# kelvin_1wire_B.net
KiCad netlist of a schematic drawn in EAGLE
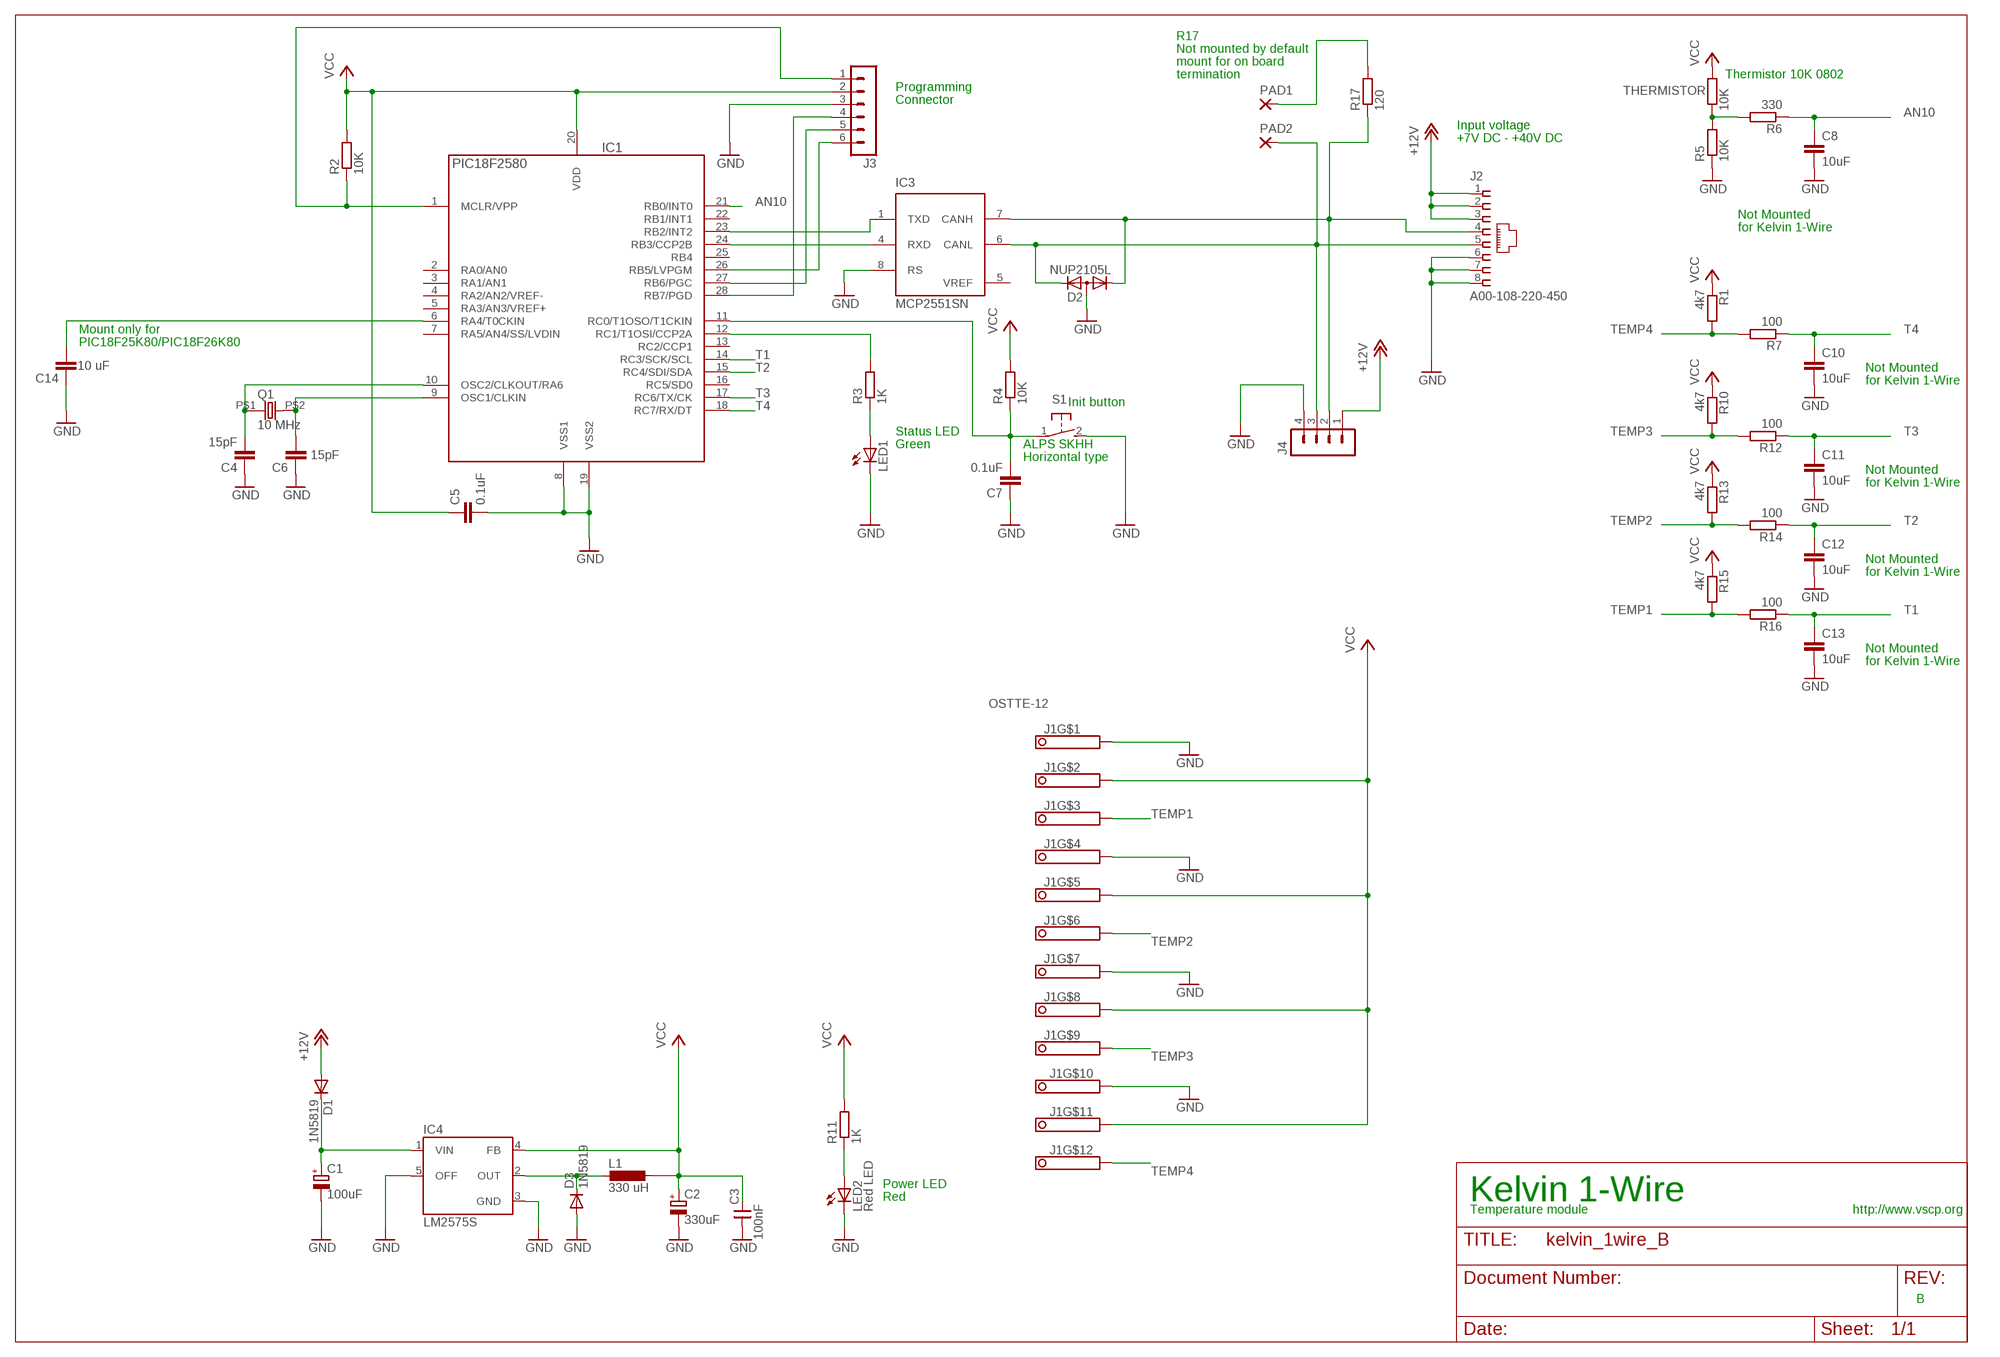
[diagram p0: schematic, sheet 1]

(export (version "E")
  (design (tool "Eeschema 10.0.6"))
  (components
    (comp (ref "C1")
      (value "100uF")
      (footprint "eagle-import:PANASONIC_D")
      (libsource (lib "eagle-import") (part "CPOL-EUD"))
    )
    (comp (ref "C2")
      (value "330uF")
      (footprint "eagle-import:PANASONIC_D")
      (libsource (lib "eagle-import") (part "CPOL-EUD"))
    )
    (comp (ref "C3")
      (value "100nF")
      (footprint "eagle-import:0805")
      (libsource (lib "eagle-import") (part "CNP-0805"))
    )
    (comp (ref "C4")
      (value "15pF")
      (footprint "eagle-import:C0805")
      (libsource (lib "eagle-import") (part "C-EUC0805"))
    )
    (comp (ref "C5")
      (value "0.1uF")
      (footprint "eagle-import:C0805")
      (libsource (lib "eagle-import") (part "C-EUC0805"))
    )
    (comp (ref "C6")
      (value "15pF")
      (footprint "eagle-import:C0805")
      (libsource (lib "eagle-import") (part "C-EUC0805"))
    )
    (comp (ref "C7")
      (value "0.1uF")
      (footprint "eagle-import:C0805")
      (libsource (lib "eagle-import") (part "C-EUC0805"))
    )
    (comp (ref "C8")
      (value "10uF")
      (footprint "eagle-import:C0805")
      (libsource (lib "eagle-import") (part "C-EUC0805"))
    )
    (comp (ref "C10")
      (value "10uF")
      (footprint "eagle-import:C0805")
      (libsource (lib "eagle-import") (part "C-EUC0805"))
    )
    (comp (ref "C11")
      (value "10uF")
      (footprint "eagle-import:C0805")
      (libsource (lib "eagle-import") (part "C-EUC0805"))
    )
    (comp (ref "C12")
      (value "10uF")
      (footprint "eagle-import:C0805")
      (libsource (lib "eagle-import") (part "C-EUC0805"))
    )
    (comp (ref "C13")
      (value "10uF")
      (footprint "eagle-import:C0805")
      (libsource (lib "eagle-import") (part "C-EUC0805"))
    )
    (comp (ref "C14")
      (value "10 uF")
      (footprint "eagle-import:C0805")
      (libsource (lib "eagle-import") (part "C-EUC0805"))
    )
    (comp (ref "D1")
      (value "1N5819")
      (footprint "eagle-import:SOD123")
      (libsource (lib "eagle-import") (part "DIODE-SOD123"))
    )
    (comp (ref "D2")
      (value "NUP2105L")
      (footprint "eagle-import:SOT23")
      (libsource (lib "eagle-import") (part "DIODE-2CA|ACSOT23"))
    )
    (comp (ref "D3")
      (value "1N5819")
      (footprint "eagle-import:SOD123")
      (libsource (lib "eagle-import") (part "DIODE-SOD123"))
    )
    (comp (ref "IC1")
      (value "PIC18F2580")
      (footprint "eagle-import:SO28")
      (libsource (lib "eagle-import") (part "PIC18F252-?I/SOL"))
    )
    (comp (ref "IC3")
      (value "MCP2551SN")
      (footprint "eagle-import:SO-08")
      (libsource (lib "eagle-import") (part "MCP2551SN"))
    )
    (comp (ref "IC4")
      (value "LM2575S")
      (footprint "eagle-import:TO263-5")
      (libsource (lib "eagle-import") (part "LM2575S"))
    )
    (comp (ref "J1")
      (value "OSTTE-12")
      (footprint "eagle-import:PINHEAD-12")
      (libsource (lib "eagle-import") (part "OSTTE-12"))
    )
    (comp (ref "J2")
      (value "A00-108-220-450")
      (footprint "eagle-import:RJ-45")
      (libsource (lib "eagle-import") (part "A00-108-220-450"))
    )
    (comp (ref "J3")
      (value "MA06-1")
      (footprint "eagle-import:MA06-1")
      (libsource (lib "eagle-import") (part "MA06-1"))
    )
    (comp (ref "J4")
      (value "MA04-1")
      (footprint "eagle-import:MA04-1")
      (libsource (lib "eagle-import") (part "MA04-1"))
    )
    (comp (ref "L1")
      (value "330 uH")
      (footprint "eagle-import:DO3316P")
      (libsource (lib "eagle-import") (part "DO3316P"))
    )
    (comp (ref "LED1")
      (value "LEDCHIP-LED0805")
      (footprint "eagle-import:CHIP-LED0805")
      (libsource (lib "eagle-import") (part "LEDCHIP-LED0805"))
    )
    (comp (ref "LED2")
      (value "Red LED")
      (footprint "eagle-import:CHIP-LED0805")
      (libsource (lib "eagle-import") (part "LEDCHIP-LED0805"))
    )
    (comp (ref "PAD1")
      (value "1,6/0,8")
      (footprint "eagle-import:1,6_0,8")
      (libsource (lib "eagle-import") (part "1,6/0,8"))
    )
    (comp (ref "PAD2")
      (value "1,6/0,8")
      (footprint "eagle-import:1,6_0,8")
      (libsource (lib "eagle-import") (part "1,6/0,8"))
    )
    (comp (ref "Q1")
      (value "10 MHz")
      (footprint "eagle-import:9C")
      (libsource (lib "eagle-import") (part "HC-49S"))
    )
    (comp (ref "R1")
      (value "4k7")
      (footprint "eagle-import:R0805")
      (libsource (lib "eagle-import") (part "R-EU_R0805"))
    )
    (comp (ref "R2")
      (value "10K")
      (footprint "eagle-import:R0805")
      (libsource (lib "eagle-import") (part "R-EU_R0805"))
    )
    (comp (ref "R3")
      (value "1K")
      (footprint "eagle-import:R0805")
      (libsource (lib "eagle-import") (part "R-EU_R0805"))
    )
    (comp (ref "R4")
      (value "10K")
      (footprint "eagle-import:R0805")
      (libsource (lib "eagle-import") (part "R-EU_R0805"))
    )
    (comp (ref "R5")
      (value "10K")
      (footprint "eagle-import:R0805")
      (libsource (lib "eagle-import") (part "R-EU_R0805"))
    )
    (comp (ref "R6")
      (value "330")
      (footprint "eagle-import:R0805")
      (libsource (lib "eagle-import") (part "R-EU_R0805"))
    )
    (comp (ref "R7")
      (value "100")
      (footprint "eagle-import:R0805")
      (libsource (lib "eagle-import") (part "R-EU_R0805"))
    )
    (comp (ref "R10")
      (value "4k7")
      (footprint "eagle-import:R0805")
      (libsource (lib "eagle-import") (part "R-EU_R0805"))
    )
    (comp (ref "R11")
      (value "1K")
      (footprint "eagle-import:R0805")
      (libsource (lib "eagle-import") (part "R-EU_R0805"))
    )
    (comp (ref "R12")
      (value "100")
      (footprint "eagle-import:R0805")
      (libsource (lib "eagle-import") (part "R-EU_R0805"))
    )
    (comp (ref "R13")
      (value "4k7")
      (footprint "eagle-import:R0805")
      (libsource (lib "eagle-import") (part "R-EU_R0805"))
    )
    (comp (ref "R14")
      (value "100")
      (footprint "eagle-import:R0805")
      (libsource (lib "eagle-import") (part "R-EU_R0805"))
    )
    (comp (ref "R15")
      (value "4k7")
      (footprint "eagle-import:R0805")
      (libsource (lib "eagle-import") (part "R-EU_R0805"))
    )
    (comp (ref "R16")
      (value "100")
      (footprint "eagle-import:R0805")
      (libsource (lib "eagle-import") (part "R-EU_R0805"))
    )
    (comp (ref "R17")
      (value "120")
      (footprint "eagle-import:R0805")
      (libsource (lib "eagle-import") (part "R-EU_R0805"))
    )
    (comp (ref "S1")
      (value "31-XX")
      (footprint "eagle-import:B3F-31XX")
      (fields (field (name "MPN") "B3F-3100"))
      (libsource (lib "eagle-import") (part "31-XX"))
    )
    (comp (ref "THERMISTOR")
      (value "10K")
      (footprint "eagle-import:R0805")
      (libsource (lib "eagle-import") (part "R-EU_R0805"))
    )
  )
  (nets
    (net (code "1") (name "+12V") (class "Default")
      (node (ref "D1") (pin "A") (pinfunction "A_A") (pintype "passive"))
      (node (ref "J2") (pin "1") (pinfunction "1_1") (pintype "passive"))
      (node (ref "J2") (pin "2") (pinfunction "2_2") (pintype "passive"))
      (node (ref "J2") (pin "3") (pinfunction "3_3") (pintype "passive"))
      (node (ref "J4") (pin "1") (pinfunction "1_1") (pintype "passive"))
    )
    (net (code "2") (name "/AN10") (class "Default")
      (node (ref "C8") (pin "1") (pinfunction "1_1") (pintype "passive"))
      (node (ref "IC1") (pin "21") (pinfunction "RB0/INT0_21") (pintype "bidirectional"))
      (node (ref "R6") (pin "1") (pinfunction "1_1") (pintype "passive"))
    )
    (net (code "3") (name "/T1") (class "Default")
      (node (ref "C13") (pin "1") (pinfunction "1_1") (pintype "passive"))
      (node (ref "IC1") (pin "14") (pinfunction "RC3/SCK/SCL_14") (pintype "bidirectional"))
      (node (ref "R16") (pin "1") (pinfunction "1_1") (pintype "passive"))
    )
    (net (code "4") (name "/T2") (class "Default")
      (node (ref "C12") (pin "1") (pinfunction "1_1") (pintype "passive"))
      (node (ref "IC1") (pin "15") (pinfunction "RC4/SDI/SDA_15") (pintype "bidirectional"))
      (node (ref "R14") (pin "1") (pinfunction "1_1") (pintype "passive"))
    )
    (net (code "5") (name "/T3") (class "Default")
      (node (ref "C11") (pin "1") (pinfunction "1_1") (pintype "passive"))
      (node (ref "IC1") (pin "17") (pinfunction "RC6/TX/CK_17") (pintype "bidirectional"))
      (node (ref "R12") (pin "1") (pinfunction "1_1") (pintype "passive"))
    )
    (net (code "6") (name "/T4") (class "Default")
      (node (ref "C10") (pin "1") (pinfunction "1_1") (pintype "passive"))
      (node (ref "IC1") (pin "18") (pinfunction "RC7/RX/DT_18") (pintype "bidirectional"))
      (node (ref "R7") (pin "1") (pinfunction "1_1") (pintype "passive"))
    )
    (net (code "7") (name "/TEMP1") (class "Default")
      (node (ref "J1") (pin "3") (pinfunction "K_3") (pintype "passive"))
      (node (ref "R15") (pin "2") (pinfunction "2_2") (pintype "passive"))
      (node (ref "R16") (pin "2") (pinfunction "2_2") (pintype "passive"))
    )
    (net (code "8") (name "/TEMP2") (class "Default")
      (node (ref "J1") (pin "6") (pinfunction "K_6") (pintype "passive"))
      (node (ref "R13") (pin "2") (pinfunction "2_2") (pintype "passive"))
      (node (ref "R14") (pin "2") (pinfunction "2_2") (pintype "passive"))
    )
    (net (code "9") (name "/TEMP3") (class "Default")
      (node (ref "J1") (pin "9") (pinfunction "K_9") (pintype "passive"))
      (node (ref "R10") (pin "2") (pinfunction "2_2") (pintype "passive"))
      (node (ref "R12") (pin "2") (pinfunction "2_2") (pintype "passive"))
    )
    (net (code "10") (name "/TEMP4") (class "Default")
      (node (ref "J1") (pin "12") (pinfunction "K_12") (pintype "passive"))
      (node (ref "R1") (pin "2") (pinfunction "2_2") (pintype "passive"))
      (node (ref "R7") (pin "2") (pinfunction "2_2") (pintype "passive"))
    )
    (net (code "11") (name "/VREF") (class "Default")
      (node (ref "IC3") (pin "5") (pinfunction "VREF_5") (pintype "power_in"))
    )
    (net (code "12") (name "GND") (class "Default")
      (node (ref "C1") (pin "-") (pinfunction "-_-") (pintype "passive"))
      (node (ref "C10") (pin "2") (pinfunction "2_2") (pintype "passive"))
      (node (ref "C11") (pin "2") (pinfunction "2_2") (pintype "passive"))
      (node (ref "C12") (pin "2") (pinfunction "2_2") (pintype "passive"))
      (node (ref "C13") (pin "2") (pinfunction "2_2") (pintype "passive"))
      (node (ref "C14") (pin "1") (pinfunction "1_1") (pintype "passive"))
      (node (ref "C2") (pin "-") (pinfunction "-_-") (pintype "passive"))
      (node (ref "C3") (pin "1") (pinfunction "1_1") (pintype "passive"))
      (node (ref "C4") (pin "1") (pinfunction "1_1") (pintype "passive"))
      (node (ref "C5") (pin "2") (pinfunction "2_2") (pintype "passive"))
      (node (ref "C6") (pin "1") (pinfunction "1_1") (pintype "passive"))
      (node (ref "C7") (pin "1") (pinfunction "1_1") (pintype "passive"))
      (node (ref "C8") (pin "2") (pinfunction "2_2") (pintype "passive"))
      (node (ref "D2") (pin "3") (pinfunction "A_3") (pintype "passive"))
      (node (ref "D3") (pin "A") (pinfunction "A_A") (pintype "passive"))
      (node (ref "IC1") (pin "19") (pinfunction "VSS2_19") (pintype "power_in"))
      (node (ref "IC1") (pin "8") (pinfunction "VSS1_8") (pintype "power_in"))
      (node (ref "IC3") (pin "8") (pinfunction "RS_8") (pintype "input"))
      (node (ref "IC4") (pin "3") (pinfunction "GND_3") (pintype "power_in"))
      (node (ref "IC4") (pin "5") (pinfunction "OFF_5") (pintype "input"))
      (node (ref "J1") (pin "1") (pinfunction "K_1") (pintype "passive"))
      (node (ref "J1") (pin "10") (pinfunction "K_10") (pintype "passive"))
      (node (ref "J1") (pin "4") (pinfunction "K_4") (pintype "passive"))
      (node (ref "J1") (pin "7") (pinfunction "K_7") (pintype "passive"))
      (node (ref "J2") (pin "6") (pinfunction "6_6") (pintype "passive"))
      (node (ref "J2") (pin "7") (pinfunction "7_7") (pintype "passive"))
      (node (ref "J2") (pin "8") (pinfunction "8_8") (pintype "passive"))
      (node (ref "J3") (pin "3") (pinfunction "3_3") (pintype "passive"))
      (node (ref "J4") (pin "4") (pinfunction "4_4") (pintype "passive"))
      (node (ref "LED1") (pin "C") (pinfunction "C_C") (pintype "passive"))
      (node (ref "LED2") (pin "C") (pinfunction "C_C") (pintype "passive"))
      (node (ref "R5") (pin "1") (pinfunction "1_1") (pintype "passive"))
      (node (ref "S1") (pin "2") (pinfunction "S_2") (pintype "passive"))
    )
    (net (code "13") (name "Net-(D2-K1)") (class "Default")
      (node (ref "D2") (pin "1") (pinfunction "K1_1") (pintype "passive"))
      (node (ref "IC3") (pin "7") (pinfunction "CANH_7") (pintype "bidirectional"))
      (node (ref "J2") (pin "4") (pinfunction "4_4") (pintype "passive"))
      (node (ref "J4") (pin "2") (pinfunction "2_2") (pintype "passive"))
      (node (ref "R17") (pin "1") (pinfunction "1_1") (pintype "passive"))
    )
    (net (code "14") (name "Net-(D2-K2)") (class "Default")
      (node (ref "D2") (pin "2") (pinfunction "K2_2") (pintype "passive"))
      (node (ref "IC3") (pin "6") (pinfunction "CANL_6") (pintype "bidirectional"))
      (node (ref "J2") (pin "5") (pinfunction "5_5") (pintype "passive"))
      (node (ref "J4") (pin "3") (pinfunction "3_3") (pintype "passive"))
      (node (ref "PAD2") (pin "1") (pinfunction "P_1") (pintype "passive"))
    )
    (net (code "15") (name "Net-(IC1-MCLR{slash}VPP)") (class "Default")
      (node (ref "IC1") (pin "1") (pinfunction "MCLR/VPP_1") (pintype "input"))
      (node (ref "J3") (pin "1") (pinfunction "1_1") (pintype "passive"))
      (node (ref "R2") (pin "1") (pinfunction "1_1") (pintype "passive"))
    )
    (net (code "16") (name "Net-(IC1-OSC1{slash}CLKIN)") (class "Default")
      (node (ref "C6") (pin "2") (pinfunction "2_2") (pintype "passive"))
      (node (ref "IC1") (pin "9") (pinfunction "OSC1/CLKIN_9") (pintype "input"))
      (node (ref "Q1") (pin "P$2") (pinfunction "2_P$2") (pintype "passive"))
    )
    (net (code "17") (name "Net-(IC1-OSC2{slash}CLKOUT{slash}RA6)") (class "Default")
      (node (ref "C4") (pin "2") (pinfunction "2_2") (pintype "passive"))
      (node (ref "IC1") (pin "10") (pinfunction "OSC2/CLKOUT/RA6_10") (pintype "output"))
      (node (ref "Q1") (pin "P$1") (pinfunction "1_P$1") (pintype "passive"))
    )
    (net (code "18") (name "Net-(IC1-RA4{slash}T0CKIN)") (class "Default")
      (node (ref "C14") (pin "2") (pinfunction "2_2") (pintype "passive"))
      (node (ref "IC1") (pin "6") (pinfunction "RA4/T0CKIN_6") (pintype "open_collector"))
    )
    (net (code "19") (name "Net-(IC1-RB2{slash}INT2)") (class "Default")
      (node (ref "IC1") (pin "23") (pinfunction "RB2/INT2_23") (pintype "bidirectional"))
      (node (ref "IC3") (pin "1") (pinfunction "TXD_1") (pintype "input"))
    )
    (net (code "20") (name "Net-(IC1-RB3{slash}CCP2B)") (class "Default")
      (node (ref "IC1") (pin "24") (pinfunction "RB3/CCP2B_24") (pintype "bidirectional"))
      (node (ref "IC3") (pin "4") (pinfunction "RXD_4") (pintype "output"))
    )
    (net (code "21") (name "Net-(IC1-RB5{slash}LVPGM)") (class "Default")
      (node (ref "IC1") (pin "26") (pinfunction "RB5/LVPGM_26") (pintype "bidirectional"))
      (node (ref "J3") (pin "6") (pinfunction "6_6") (pintype "passive"))
    )
    (net (code "22") (name "Net-(IC1-RB6{slash}PGC)") (class "Default")
      (node (ref "IC1") (pin "27") (pinfunction "RB6/PGC_27") (pintype "bidirectional"))
      (node (ref "J3") (pin "5") (pinfunction "5_5") (pintype "passive"))
    )
    (net (code "23") (name "Net-(IC1-RB7{slash}PGD)") (class "Default")
      (node (ref "IC1") (pin "28") (pinfunction "RB7/PGD_28") (pintype "bidirectional"))
      (node (ref "J3") (pin "4") (pinfunction "4_4") (pintype "passive"))
    )
    (net (code "24") (name "Net-(IC1-RC0{slash}T1OSO{slash}T1CKIN)") (class "Default")
      (node (ref "C7") (pin "2") (pinfunction "2_2") (pintype "passive"))
      (node (ref "IC1") (pin "11") (pinfunction "RC0/T1OSO/T1CKIN_11") (pintype "bidirectional"))
      (node (ref "R4") (pin "1") (pinfunction "1_1") (pintype "passive"))
      (node (ref "S1") (pin "1") (pinfunction "P_1") (pintype "passive"))
    )
    (net (code "25") (name "Net-(IC1-RC1{slash}T1OSI{slash}CCP2A)") (class "Default")
      (node (ref "IC1") (pin "12") (pinfunction "RC1/T1OSI/CCP2A_12") (pintype "bidirectional"))
      (node (ref "R3") (pin "2") (pinfunction "2_2") (pintype "passive"))
    )
    (net (code "26") (name "Net-(IC4-OUT)") (class "Default")
      (node (ref "D3") (pin "C") (pinfunction "C_C") (pintype "passive"))
      (node (ref "IC4") (pin "2") (pinfunction "OUT_2") (pintype "output"))
      (node (ref "L1") (pin "1") (pinfunction "1_1") (pintype "passive"))
    )
    (net (code "27") (name "Net-(IC4-VIN)") (class "Default")
      (node (ref "C1") (pin "+") (pinfunction "+_+") (pintype "passive"))
      (node (ref "D1") (pin "C") (pinfunction "C_C") (pintype "passive"))
      (node (ref "IC4") (pin "1") (pinfunction "VIN_1") (pintype "power_in"))
    )
    (net (code "28") (name "Net-(LED1-PadA)") (class "Default")
      (node (ref "LED1") (pin "A") (pinfunction "A_A") (pintype "passive"))
      (node (ref "R3") (pin "1") (pinfunction "1_1") (pintype "passive"))
    )
    (net (code "29") (name "Net-(LED2-PadA)") (class "Default")
      (node (ref "LED2") (pin "A") (pinfunction "A_A") (pintype "passive"))
      (node (ref "R11") (pin "1") (pinfunction "1_1") (pintype "passive"))
    )
    (net (code "30") (name "Net-(PAD1-P)") (class "Default")
      (node (ref "PAD1") (pin "1") (pinfunction "P_1") (pintype "passive"))
      (node (ref "R17") (pin "2") (pinfunction "2_2") (pintype "passive"))
    )
    (net (code "31") (name "Net-(R5-Pad2)") (class "Default")
      (node (ref "R5") (pin "2") (pinfunction "2_2") (pintype "passive"))
      (node (ref "R6") (pin "2") (pinfunction "2_2") (pintype "passive"))
      (node (ref "THERMISTOR") (pin "1") (pinfunction "1_1") (pintype "passive"))
    )
    (net (code "32") (name "VCC") (class "Default")
      (node (ref "C2") (pin "+") (pinfunction "+_+") (pintype "passive"))
      (node (ref "C3") (pin "2") (pinfunction "2_2") (pintype "passive"))
      (node (ref "C5") (pin "1") (pinfunction "1_1") (pintype "passive"))
      (node (ref "IC1") (pin "20") (pinfunction "VDD_20") (pintype "power_in"))
      (node (ref "IC4") (pin "4") (pinfunction "FB_4") (pintype "input"))
      (node (ref "J1") (pin "11") (pinfunction "K_11") (pintype "passive"))
      (node (ref "J1") (pin "2") (pinfunction "K_2") (pintype "passive"))
      (node (ref "J1") (pin "5") (pinfunction "K_5") (pintype "passive"))
      (node (ref "J1") (pin "8") (pinfunction "K_8") (pintype "passive"))
      (node (ref "J3") (pin "2") (pinfunction "2_2") (pintype "passive"))
      (node (ref "L1") (pin "2") (pinfunction "2_2") (pintype "passive"))
      (node (ref "R1") (pin "1") (pinfunction "1_1") (pintype "passive"))
      (node (ref "R10") (pin "1") (pinfunction "1_1") (pintype "passive"))
      (node (ref "R11") (pin "2") (pinfunction "2_2") (pintype "passive"))
      (node (ref "R13") (pin "1") (pinfunction "1_1") (pintype "passive"))
      (node (ref "R15") (pin "1") (pinfunction "1_1") (pintype "passive"))
      (node (ref "R2") (pin "2") (pinfunction "2_2") (pintype "passive"))
      (node (ref "R4") (pin "2") (pinfunction "2_2") (pintype "passive"))
      (node (ref "THERMISTOR") (pin "2") (pinfunction "2_2") (pintype "passive"))
    )
    (net (code "33") (name "unconnected-(IC1-RA0{slash}AN0-Pad2)") (class "Default")
      (node (ref "IC1") (pin "2") (pinfunction "RA0/AN0_2") (pintype "bidirectional"))
    )
    (net (code "34") (name "unconnected-(IC1-RA1{slash}AN1-Pad3)") (class "Default")
      (node (ref "IC1") (pin "3") (pinfunction "RA1/AN1_3") (pintype "bidirectional"))
    )
    (net (code "35") (name "unconnected-(IC1-RA2{slash}AN2{slash}VREF--Pad4)") (class "Default")
      (node (ref "IC1") (pin "4") (pinfunction "RA2/AN2/VREF-_4") (pintype "bidirectional"))
    )
    (net (code "36") (name "unconnected-(IC1-RA3{slash}AN3{slash}VREF+-Pad5)") (class "Default")
      (node (ref "IC1") (pin "5") (pinfunction "RA3/AN3/VREF+_5") (pintype "bidirectional"))
    )
    (net (code "37") (name "unconnected-(IC1-RA5{slash}AN4{slash}SS{slash}LVDIN-Pad7)") (class "Default")
      (node (ref "IC1") (pin "7") (pinfunction "RA5/AN4/SS/LVDIN_7") (pintype "bidirectional"))
    )
    (net (code "38") (name "unconnected-(IC1-RB1{slash}INT1-Pad22)") (class "Default")
      (node (ref "IC1") (pin "22") (pinfunction "RB1/INT1_22") (pintype "bidirectional"))
    )
    (net (code "39") (name "unconnected-(IC1-RB4-Pad25)") (class "Default")
      (node (ref "IC1") (pin "25") (pinfunction "RB4_25") (pintype "bidirectional"))
    )
    (net (code "40") (name "unconnected-(IC1-RC2{slash}CCP1-Pad13)") (class "Default")
      (node (ref "IC1") (pin "13") (pinfunction "RC2/CCP1_13") (pintype "bidirectional"))
    )
    (net (code "41") (name "unconnected-(IC1-RC5{slash}SD0-Pad16)") (class "Default")
      (node (ref "IC1") (pin "16") (pinfunction "RC5/SD0_16") (pintype "bidirectional"))
    )
  )
)
